# sai.net
KiCad netlist of a schematic drawn in Altium Designer
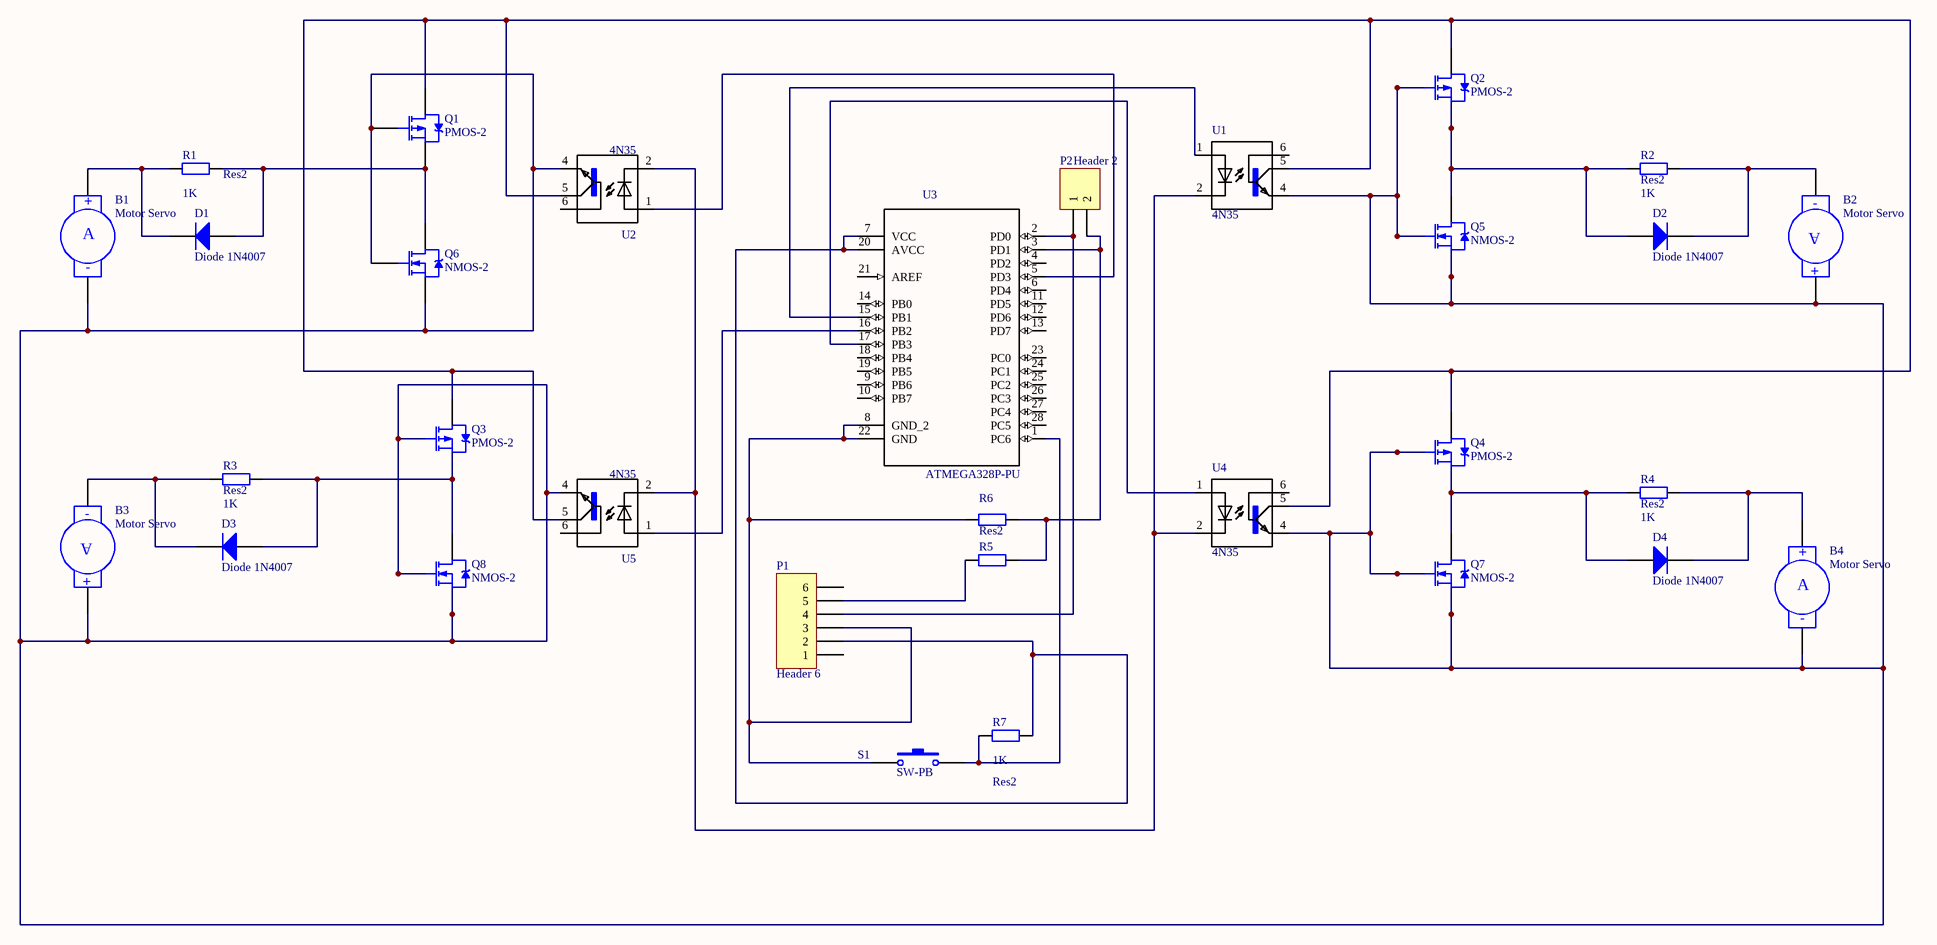
[diagram p0: sai.SchDoc]

(export (version "E")
  (design (tool "Eeschema 10.0.6"))
  (components
    (comp (ref "B1")
      (value "Motor Servo")
      (footprint "RAD-0.4")
      (description "Servo Motor")
      (fields (field (name "PUBLISHER") "Altium Limited"))
      (libsource (lib "Miscellaneous Devices") (part "Motor Servo"))
    )
    (comp (ref "B2")
      (value "Motor Servo")
      (footprint "RAD-0.4")
      (description "Servo Motor")
      (fields (field (name "PUBLISHER") "Altium Limited"))
      (libsource (lib "Miscellaneous Devices") (part "Motor Servo"))
    )
    (comp (ref "B3")
      (value "Motor Servo")
      (footprint "RAD-0.4")
      (description "Servo Motor")
      (fields (field (name "PUBLISHER") "Altium Limited"))
      (libsource (lib "Miscellaneous Devices") (part "Motor Servo"))
    )
    (comp (ref "B4")
      (value "Motor Servo")
      (footprint "RAD-0.4")
      (description "Servo Motor")
      (fields (field (name "PUBLISHER") "Altium Limited"))
      (libsource (lib "Miscellaneous Devices") (part "Motor Servo"))
    )
    (comp (ref "D1")
      (value "Diode 1N4007")
      (footprint "DO-41")
      (description "1 Amp General Purpose Rectifier")
      (fields (field (name "PUBLISHER") "Altium Limited"))
      (libsource (lib "Miscellaneous Devices") (part "Diode 1N4007"))
    )
    (comp (ref "D2")
      (value "Diode 1N4007")
      (footprint "DO-41")
      (description "1 Amp General Purpose Rectifier")
      (fields (field (name "PUBLISHER") "Altium Limited"))
      (libsource (lib "Miscellaneous Devices") (part "Diode 1N4007"))
    )
    (comp (ref "D3")
      (value "Diode 1N4007")
      (footprint "DO-41")
      (description "1 Amp General Purpose Rectifier")
      (fields (field (name "PUBLISHER") "Altium Limited"))
      (libsource (lib "Miscellaneous Devices") (part "Diode 1N4007"))
    )
    (comp (ref "D4")
      (value "Diode 1N4007")
      (footprint "DO-41")
      (description "1 Amp General Purpose Rectifier")
      (fields (field (name "PUBLISHER") "Altium Limited"))
      (libsource (lib "Miscellaneous Devices") (part "Diode 1N4007"))
    )
    (comp (ref "P1")
      (value "Header 6")
      (footprint "HDR1X6")
      (description "Header, 6-Pin")
      (fields (field (name "PUBLISHER") "Altium Limited"))
      (libsource (lib "Miscellaneous Connectors") (part "Header 6"))
    )
    (comp (ref "P2")
      (value "Header 2")
      (footprint "HDR1X2")
      (description "Header, 2-Pin")
      (fields (field (name "PUBLISHER") "Altium Limited"))
      (libsource (lib "Miscellaneous Connectors") (part "Header 2"))
    )
    (comp (ref "Q1")
      (value "PMOS-2")
      (footprint "TO-220AB")
      (description "P-Channel Power MOSFET")
      (fields (field (name "PUBLISHER") "Altium Limited"))
      (libsource (lib "Miscellaneous Devices") (part "PMOS-2"))
    )
    (comp (ref "Q2")
      (value "PMOS-2")
      (footprint "TO-220AB")
      (description "P-Channel Power MOSFET")
      (fields (field (name "PUBLISHER") "Altium Limited"))
      (libsource (lib "Miscellaneous Devices") (part "PMOS-2"))
    )
    (comp (ref "Q3")
      (value "PMOS-2")
      (footprint "TO-220AB")
      (description "P-Channel Power MOSFET")
      (fields (field (name "PUBLISHER") "Altium Limited"))
      (libsource (lib "Miscellaneous Devices") (part "PMOS-2"))
    )
    (comp (ref "Q4")
      (value "PMOS-2")
      (footprint "TO-220AB")
      (description "P-Channel Power MOSFET")
      (fields (field (name "PUBLISHER") "Altium Limited"))
      (libsource (lib "Miscellaneous Devices") (part "PMOS-2"))
    )
    (comp (ref "Q5")
      (value "NMOS-2")
      (footprint "TO-220AB")
      (description "N-Channel Power MOSFET")
      (fields (field (name "PUBLISHER") "Altium Limited"))
      (libsource (lib "Miscellaneous Devices") (part "NMOS-2"))
    )
    (comp (ref "Q6")
      (value "NMOS-2")
      (footprint "TO-220AB")
      (description "N-Channel Power MOSFET")
      (fields (field (name "PUBLISHER") "Altium Limited"))
      (libsource (lib "Miscellaneous Devices") (part "NMOS-2"))
    )
    (comp (ref "Q7")
      (value "NMOS-2")
      (footprint "TO-220AB")
      (description "N-Channel Power MOSFET")
      (fields (field (name "PUBLISHER") "Altium Limited"))
      (libsource (lib "Miscellaneous Devices") (part "NMOS-2"))
    )
    (comp (ref "Q8")
      (value "NMOS-2")
      (footprint "TO-220AB")
      (description "N-Channel Power MOSFET")
      (fields (field (name "PUBLISHER") "Altium Limited"))
      (libsource (lib "Miscellaneous Devices") (part "NMOS-2"))
    )
    (comp (ref "R1")
      (value "Res2")
      (footprint "AXIAL-0.4")
      (description "Resistor")
      (fields (field (name "ALTIUM_VALUE") "1K") (field (name "PUBLISHER") "Altium Limited"))
      (libsource (lib "Miscellaneous Devices") (part "Res2"))
    )
    (comp (ref "R2")
      (value "Res2")
      (footprint "AXIAL-0.4")
      (description "Resistor")
      (fields (field (name "ALTIUM_VALUE") "1K") (field (name "PUBLISHER") "Altium Limited"))
      (libsource (lib "Miscellaneous Devices") (part "Res2"))
    )
    (comp (ref "R3")
      (value "Res2")
      (footprint "AXIAL-0.4")
      (description "Resistor")
      (fields (field (name "ALTIUM_VALUE") "1K") (field (name "PUBLISHER") "Altium Limited"))
      (libsource (lib "Miscellaneous Devices") (part "Res2"))
    )
    (comp (ref "R4")
      (value "Res2")
      (footprint "AXIAL-0.4")
      (description "Resistor")
      (fields (field (name "ALTIUM_VALUE") "1K") (field (name "PUBLISHER") "Altium Limited"))
      (libsource (lib "Miscellaneous Devices") (part "Res2"))
    )
    (comp (ref "R5")
      (value "Res2")
      (footprint "AXIAL-0.4")
      (description "Resistor")
      (fields (field (name "PUBLISHER") "Altium Limited"))
      (libsource (lib "") (part "Res2_1"))
    )
    (comp (ref "R6")
      (value "Res2")
      (footprint "AXIAL-0.4")
      (description "Resistor")
      (fields (field (name "PUBLISHER") "Altium Limited"))
      (libsource (lib "Miscellaneous Devices") (part "Res2"))
    )
    (comp (ref "R7")
      (value "Res2")
      (footprint "AXIAL-0.4")
      (description "Resistor")
      (fields (field (name "ALTIUM_VALUE") "1K") (field (name "PUBLISHER") "Altium Limited"))
      (libsource (lib "Miscellaneous Devices") (part "Res2"))
    )
    (comp (ref "S1")
      (value "SW-PB")
      (footprint "SPST-2")
      (description "Switch")
      (fields (field (name "PUBLISHER") "Altium Limited"))
      (libsource (lib "Miscellaneous Devices") (part "SW-PB"))
    )
    (comp (ref "U1")
      (value "4N35")
      (footprint "*DIL06")
      (description "Optoisolator; Analog; 6-Pin DIP; Transistor; 6 PIN SINGLE; 100% CTR;")
      (fields (field (name "MF") "Vishay Semiconductor"))
      (libsource (lib "4N35") (part "4N35"))
    )
    (comp (ref "U2")
      (value "4N35")
      (footprint "*DIL06")
      (description "Optoisolator; Analog; 6-Pin DIP; Transistor; 6 PIN SINGLE; 100% CTR;")
      (fields (field (name "MF") "Vishay Semiconductor"))
      (libsource (lib "4N35") (part "4N35"))
    )
    (comp (ref "U3")
      (value "ATMEGA328P-PU")
      (footprint "*DIP254P762X457-28")
      (description "Embedded microcontroller ATMEGA328P-PU PDIP 28 Microchip Technology 8-Bit 20 MHz I/O number 23")
      (fields (field (name "MF") "Microchip"))
      (libsource (lib "ATMEGA328P-PU") (part "ATMEGA328P-PU"))
    )
    (comp (ref "U4")
      (value "4N35")
      (footprint "*DIL06")
      (description "Optoisolator; Analog; 6-Pin DIP; Transistor; 6 PIN SINGLE; 100% CTR;")
      (fields (field (name "MF") "Vishay Semiconductor"))
      (libsource (lib "4N35") (part "4N35"))
    )
    (comp (ref "U5")
      (value "4N35")
      (footprint "*DIL06")
      (description "Optoisolator; Analog; 6-Pin DIP; Transistor; 6 PIN SINGLE; 100% CTR;")
      (fields (field (name "MF") "Vishay Semiconductor"))
      (libsource (lib "4N35") (part "4N35"))
    )
  )
  (nets
    (net (code "1") (name "Net-(B1-+)") (class "Default")
      (node (ref "B1") (pin "1") (pinfunction "+_1") (pintype "passive"))
      (node (ref "D1") (pin "2") (pinfunction "K_2") (pintype "passive"))
      (node (ref "R1") (pin "1") (pinfunction "1_1") (pintype "passive"))
    )
    (net (code "2") (name "Net-(B1--)") (class "Default")
      (node (ref "B1") (pin "2") (pinfunction "-_2") (pintype "passive"))
      (node (ref "B2") (pin "1") (pinfunction "+_1") (pintype "passive"))
      (node (ref "B3") (pin "1") (pinfunction "+_1") (pintype "passive"))
      (node (ref "B4") (pin "2") (pinfunction "-_2") (pintype "passive"))
      (node (ref "Q1") (pin "1") (pinfunction "G_1") (pintype "passive"))
      (node (ref "Q2") (pin "1") (pinfunction "G_1") (pintype "passive"))
      (node (ref "Q3") (pin "1") (pinfunction "G_1") (pintype "passive"))
      (node (ref "Q4") (pin "1") (pinfunction "G_1") (pintype "passive"))
      (node (ref "Q5") (pin "1") (pinfunction "G_1") (pintype "passive"))
      (node (ref "Q5") (pin "3") (pinfunction "S_3") (pintype "passive"))
      (node (ref "Q6") (pin "1") (pinfunction "G_1") (pintype "passive"))
      (node (ref "Q6") (pin "3") (pinfunction "S_3") (pintype "passive"))
      (node (ref "Q7") (pin "1") (pinfunction "G_1") (pintype "passive"))
      (node (ref "Q7") (pin "3") (pinfunction "S_3") (pintype "passive"))
      (node (ref "Q8") (pin "1") (pinfunction "G_1") (pintype "passive"))
      (node (ref "Q8") (pin "3") (pinfunction "S_3") (pintype "passive"))
      (node (ref "U1") (pin "4") (pinfunction "EMI_4") (pintype "passive"))
      (node (ref "U2") (pin "4") (pinfunction "EMI_4") (pintype "passive"))
      (node (ref "U4") (pin "4") (pinfunction "EMI_4") (pintype "passive"))
      (node (ref "U5") (pin "4") (pinfunction "EMI_4") (pintype "passive"))
    )
    (net (code "3") (name "Net-(B2--)") (class "Default")
      (node (ref "B2") (pin "2") (pinfunction "-_2") (pintype "passive"))
      (node (ref "D2") (pin "2") (pinfunction "K_2") (pintype "passive"))
      (node (ref "R2") (pin "2") (pinfunction "2_2") (pintype "passive"))
    )
    (net (code "4") (name "Net-(B3--)") (class "Default")
      (node (ref "B3") (pin "2") (pinfunction "-_2") (pintype "passive"))
      (node (ref "D3") (pin "2") (pinfunction "K_2") (pintype "passive"))
      (node (ref "R3") (pin "1") (pinfunction "1_1") (pintype "passive"))
    )
    (net (code "5") (name "Net-(B4-+)") (class "Default")
      (node (ref "B4") (pin "1") (pinfunction "+_1") (pintype "passive"))
      (node (ref "D4") (pin "2") (pinfunction "K_2") (pintype "passive"))
      (node (ref "R4") (pin "2") (pinfunction "2_2") (pintype "passive"))
    )
    (net (code "6") (name "Net-(D1-A)") (class "Default")
      (node (ref "D1") (pin "1") (pinfunction "A_1") (pintype "passive"))
      (node (ref "Q1") (pin "3") (pinfunction "S_3") (pintype "passive"))
      (node (ref "Q6") (pin "2") (pinfunction "D_2") (pintype "passive"))
      (node (ref "R1") (pin "2") (pinfunction "2_2") (pintype "passive"))
    )
    (net (code "7") (name "Net-(D2-A)") (class "Default")
      (node (ref "D2") (pin "1") (pinfunction "A_1") (pintype "passive"))
      (node (ref "Q2") (pin "3") (pinfunction "S_3") (pintype "passive"))
      (node (ref "Q5") (pin "2") (pinfunction "D_2") (pintype "passive"))
      (node (ref "R2") (pin "1") (pinfunction "1_1") (pintype "passive"))
    )
    (net (code "8") (name "Net-(D3-A)") (class "Default")
      (node (ref "D3") (pin "1") (pinfunction "A_1") (pintype "passive"))
      (node (ref "Q3") (pin "3") (pinfunction "S_3") (pintype "passive"))
      (node (ref "Q8") (pin "2") (pinfunction "D_2") (pintype "passive"))
      (node (ref "R3") (pin "2") (pinfunction "2_2") (pintype "passive"))
    )
    (net (code "9") (name "Net-(D4-A)") (class "Default")
      (node (ref "D4") (pin "1") (pinfunction "A_1") (pintype "passive"))
      (node (ref "Q4") (pin "3") (pinfunction "S_3") (pintype "passive"))
      (node (ref "Q7") (pin "2") (pinfunction "D_2") (pintype "passive"))
      (node (ref "R4") (pin "1") (pinfunction "1_1") (pintype "passive"))
    )
    (net (code "10") (name "Net-(P1-Pad5)") (class "Default")
      (node (ref "P1") (pin "5") (pinfunction "5_5") (pintype "passive"))
      (node (ref "R5") (pin "2") (pinfunction "2_2") (pintype "passive"))
    )
    (net (code "11") (name "Net-(Q1-D)") (class "Default")
      (node (ref "Q1") (pin "2") (pinfunction "D_2") (pintype "passive"))
      (node (ref "Q2") (pin "2") (pinfunction "D_2") (pintype "passive"))
      (node (ref "Q3") (pin "2") (pinfunction "D_2") (pintype "passive"))
      (node (ref "Q4") (pin "2") (pinfunction "D_2") (pintype "passive"))
      (node (ref "U1") (pin "5") (pinfunction "COL_5") (pintype "passive"))
      (node (ref "U2") (pin "5") (pinfunction "COL_5") (pintype "passive"))
      (node (ref "U4") (pin "5") (pinfunction "COL_5") (pintype "passive"))
      (node (ref "U5") (pin "5") (pinfunction "COL_5") (pintype "passive"))
    )
    (net (code "12") (name "Net-(U1-A)") (class "Default")
      (node (ref "U1") (pin "1") (pinfunction "A_1") (pintype "passive"))
      (node (ref "U3") (pin "15") (pinfunction "PB1_15") (pintype "bidirectional"))
    )
    (net (code "13") (name "Net-(U1-C)") (class "Default")
      (node (ref "U1") (pin "2") (pinfunction "C_2") (pintype "passive"))
      (node (ref "U2") (pin "2") (pinfunction "C_2") (pintype "passive"))
      (node (ref "U4") (pin "2") (pinfunction "C_2") (pintype "passive"))
      (node (ref "U5") (pin "2") (pinfunction "C_2") (pintype "passive"))
    )
    (net (code "14") (name "Net-(U2-A)") (class "Default")
      (node (ref "U2") (pin "1") (pinfunction "A_1") (pintype "passive"))
      (node (ref "U3") (pin "5") (pinfunction "PD3_5") (pintype "bidirectional"))
    )
    (net (code "15") (name "Net-(U3-AVCC)") (class "Default")
      (node (ref "P1") (pin "2") (pinfunction "2_2") (pintype "passive"))
      (node (ref "R7") (pin "2") (pinfunction "2_2") (pintype "passive"))
      (node (ref "U3") (pin "20") (pinfunction "AVCC_20") (pintype "power_in"))
      (node (ref "U3") (pin "7") (pinfunction "VCC_7") (pintype "power_in"))
    )
    (net (code "16") (name "Net-(U3-GND)") (class "Default")
      (node (ref "P1") (pin "3") (pinfunction "3_3") (pintype "passive"))
      (node (ref "R6") (pin "1") (pinfunction "1_1") (pintype "passive"))
      (node (ref "S1") (pin "1") (pinfunction "1_1") (pintype "passive"))
      (node (ref "U3") (pin "22") (pinfunction "GND_22") (pintype "passive"))
      (node (ref "U3") (pin "8") (pinfunction "GND_2_8") (pintype "passive"))
    )
    (net (code "17") (name "Net-(U3-PB2)") (class "Default")
      (node (ref "U3") (pin "16") (pinfunction "PB2_16") (pintype "bidirectional"))
      (node (ref "U5") (pin "1") (pinfunction "A_1") (pintype "passive"))
    )
    (net (code "18") (name "Net-(U3-PB3)") (class "Default")
      (node (ref "U3") (pin "17") (pinfunction "PB3_17") (pintype "bidirectional"))
      (node (ref "U4") (pin "1") (pinfunction "A_1") (pintype "passive"))
    )
    (net (code "19") (name "Net-(U3-PC6)") (class "Default")
      (node (ref "R7") (pin "1") (pinfunction "1_1") (pintype "passive"))
      (node (ref "S1") (pin "2") (pinfunction "2_2") (pintype "passive"))
      (node (ref "U3") (pin "1") (pinfunction "PC6_1") (pintype "bidirectional"))
    )
    (net (code "20") (name "Net-(U3-PD0)") (class "Default")
      (node (ref "P1") (pin "4") (pinfunction "4_4") (pintype "passive"))
      (node (ref "P2") (pin "1") (pinfunction "1_1") (pintype "passive"))
      (node (ref "U3") (pin "2") (pinfunction "PD0_2") (pintype "bidirectional"))
    )
    (net (code "21") (name "Net-(U3-PD1)") (class "Default")
      (node (ref "P2") (pin "2") (pinfunction "2_2") (pintype "passive"))
      (node (ref "R5") (pin "1") (pinfunction "1_1") (pintype "passive"))
      (node (ref "R6") (pin "2") (pinfunction "2_2") (pintype "passive"))
      (node (ref "U3") (pin "3") (pinfunction "PD1_3") (pintype "bidirectional"))
    )
    (net (code "22") (name "unconnected-(P1-Pad1)") (class "Default")
      (node (ref "P1") (pin "1") (pinfunction "1_1") (pintype "passive"))
    )
    (net (code "23") (name "unconnected-(P1-Pad6)") (class "Default")
      (node (ref "P1") (pin "6") (pinfunction "6_6") (pintype "passive"))
    )
    (net (code "24") (name "unconnected-(U1-BAS-Pad6)") (class "Default")
      (node (ref "U1") (pin "6") (pinfunction "BAS_6") (pintype "passive"))
    )
    (net (code "25") (name "unconnected-(U2-BAS-Pad6)") (class "Default")
      (node (ref "U2") (pin "6") (pinfunction "BAS_6") (pintype "passive"))
    )
    (net (code "26") (name "unconnected-(U3-AREF-Pad21)") (class "Default")
      (node (ref "U3") (pin "21") (pinfunction "AREF_21") (pintype "input"))
    )
    (net (code "27") (name "unconnected-(U3-PB0-Pad14)") (class "Default")
      (node (ref "U3") (pin "14") (pinfunction "PB0_14") (pintype "bidirectional"))
    )
    (net (code "28") (name "unconnected-(U3-PB4-Pad18)") (class "Default")
      (node (ref "U3") (pin "18") (pinfunction "PB4_18") (pintype "bidirectional"))
    )
    (net (code "29") (name "unconnected-(U3-PB5-Pad19)") (class "Default")
      (node (ref "U3") (pin "19") (pinfunction "PB5_19") (pintype "bidirectional"))
    )
    (net (code "30") (name "unconnected-(U3-PB6-Pad9)") (class "Default")
      (node (ref "U3") (pin "9") (pinfunction "PB6_9") (pintype "bidirectional"))
    )
    (net (code "31") (name "unconnected-(U3-PB7-Pad10)") (class "Default")
      (node (ref "U3") (pin "10") (pinfunction "PB7_10") (pintype "bidirectional"))
    )
    (net (code "32") (name "unconnected-(U3-PC0-Pad23)") (class "Default")
      (node (ref "U3") (pin "23") (pinfunction "PC0_23") (pintype "bidirectional"))
    )
    (net (code "33") (name "unconnected-(U3-PC1-Pad24)") (class "Default")
      (node (ref "U3") (pin "24") (pinfunction "PC1_24") (pintype "bidirectional"))
    )
    (net (code "34") (name "unconnected-(U3-PC2-Pad25)") (class "Default")
      (node (ref "U3") (pin "25") (pinfunction "PC2_25") (pintype "bidirectional"))
    )
    (net (code "35") (name "unconnected-(U3-PC3-Pad26)") (class "Default")
      (node (ref "U3") (pin "26") (pinfunction "PC3_26") (pintype "bidirectional"))
    )
    (net (code "36") (name "unconnected-(U3-PC4-Pad27)") (class "Default")
      (node (ref "U3") (pin "27") (pinfunction "PC4_27") (pintype "bidirectional"))
    )
    (net (code "37") (name "unconnected-(U3-PC5-Pad28)") (class "Default")
      (node (ref "U3") (pin "28") (pinfunction "PC5_28") (pintype "bidirectional"))
    )
    (net (code "38") (name "unconnected-(U3-PD2-Pad4)") (class "Default")
      (node (ref "U3") (pin "4") (pinfunction "PD2_4") (pintype "bidirectional"))
    )
    (net (code "39") (name "unconnected-(U3-PD4-Pad6)") (class "Default")
      (node (ref "U3") (pin "6") (pinfunction "PD4_6") (pintype "bidirectional"))
    )
    (net (code "40") (name "unconnected-(U3-PD5-Pad11)") (class "Default")
      (node (ref "U3") (pin "11") (pinfunction "PD5_11") (pintype "bidirectional"))
    )
    (net (code "41") (name "unconnected-(U3-PD6-Pad12)") (class "Default")
      (node (ref "U3") (pin "12") (pinfunction "PD6_12") (pintype "bidirectional"))
    )
    (net (code "42") (name "unconnected-(U3-PD7-Pad13)") (class "Default")
      (node (ref "U3") (pin "13") (pinfunction "PD7_13") (pintype "bidirectional"))
    )
    (net (code "43") (name "unconnected-(U4-BAS-Pad6)") (class "Default")
      (node (ref "U4") (pin "6") (pinfunction "BAS_6") (pintype "passive"))
    )
    (net (code "44") (name "unconnected-(U5-BAS-Pad6)") (class "Default")
      (node (ref "U5") (pin "6") (pinfunction "BAS_6") (pintype "passive"))
    )
  )
)
